# Spectra6PCB_83.net
KiCad netlist of a schematic drawn in EAGLE
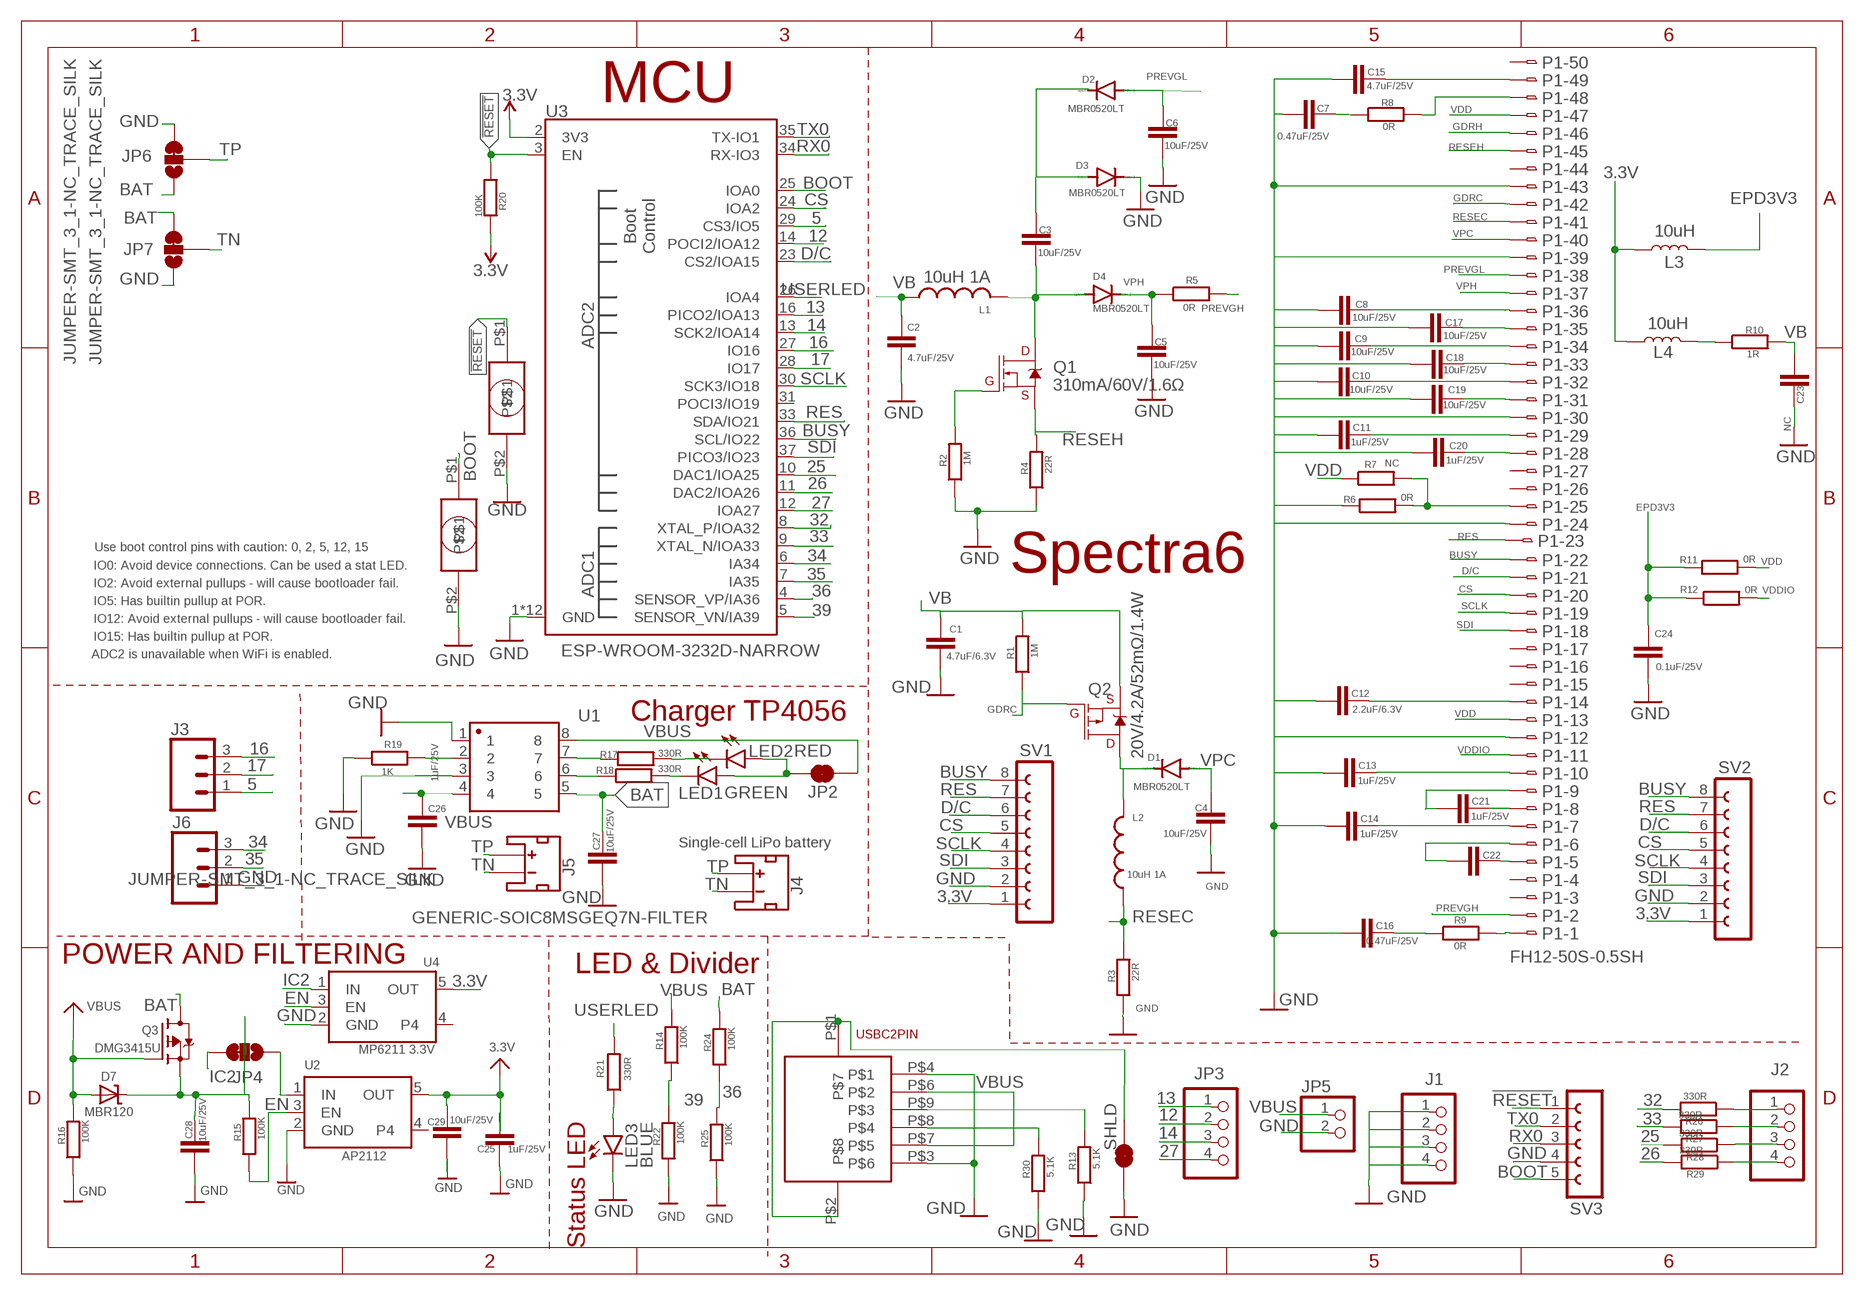
[diagram p0: schematic, sheet 1]

(export (version "E")
  (design (tool "Eeschema 10.0.6"))
  (components
    (comp (ref "C1")
      (value "4.7uF/6.3V")
      (footprint "eagle-import:C0805")
      (libsource (lib "eagle-import") (part "C-EUC0805"))
    )
    (comp (ref "C2")
      (value "4.7uF/25V")
      (footprint "eagle-import:C0805")
      (libsource (lib "eagle-import") (part "C-EUC0805"))
    )
    (comp (ref "C3")
      (value "10uF/25V")
      (footprint "eagle-import:C0805")
      (libsource (lib "eagle-import") (part "C-EUC0805"))
    )
    (comp (ref "C4")
      (value "10uF/25V")
      (footprint "eagle-import:C0805")
      (libsource (lib "eagle-import") (part "C-EUC0805"))
    )
    (comp (ref "C5")
      (value "10uF/25V")
      (footprint "eagle-import:C0805")
      (libsource (lib "eagle-import") (part "C-EUC0805"))
    )
    (comp (ref "C6")
      (value "10uF/25V")
      (footprint "eagle-import:C0805")
      (libsource (lib "eagle-import") (part "C-EUC0805"))
    )
    (comp (ref "C7")
      (value "0.47uF/25V")
      (footprint "eagle-import:C0805")
      (libsource (lib "eagle-import") (part "C-EUC0805"))
    )
    (comp (ref "C8")
      (value "10uF/25V")
      (footprint "eagle-import:C0805")
      (libsource (lib "eagle-import") (part "C-EUC0805"))
    )
    (comp (ref "C9")
      (value "10uF/25V")
      (footprint "eagle-import:C0805")
      (libsource (lib "eagle-import") (part "C-EUC0805"))
    )
    (comp (ref "C10")
      (value "10uF/25V")
      (footprint "eagle-import:C0805")
      (libsource (lib "eagle-import") (part "C-EUC0805"))
    )
    (comp (ref "C11")
      (value "1uF/25V")
      (footprint "eagle-import:C0805")
      (libsource (lib "eagle-import") (part "C-EUC0805"))
    )
    (comp (ref "C12")
      (value "2.2uF/6.3V")
      (footprint "eagle-import:C0805")
      (libsource (lib "eagle-import") (part "C-EUC0805"))
    )
    (comp (ref "C13")
      (value "1uF/25V")
      (footprint "eagle-import:C0805")
      (libsource (lib "eagle-import") (part "C-EUC0805"))
    )
    (comp (ref "C14")
      (value "1uF/25V")
      (footprint "eagle-import:C0805")
      (libsource (lib "eagle-import") (part "C-EUC0805"))
    )
    (comp (ref "C15")
      (value "4.7uF/25V")
      (footprint "eagle-import:C0805")
      (libsource (lib "eagle-import") (part "C-EUC0805"))
    )
    (comp (ref "C16")
      (value "0.47uF/25V")
      (footprint "eagle-import:C0805")
      (libsource (lib "eagle-import") (part "C-EUC0805"))
    )
    (comp (ref "C17")
      (value "10uF/25V")
      (footprint "eagle-import:C0805")
      (libsource (lib "eagle-import") (part "C-EUC0805"))
    )
    (comp (ref "C18")
      (value "10uF/25V")
      (footprint "eagle-import:C0805")
      (libsource (lib "eagle-import") (part "C-EUC0805"))
    )
    (comp (ref "C19")
      (value "10uF/25V")
      (footprint "eagle-import:C0805")
      (libsource (lib "eagle-import") (part "C-EUC0805"))
    )
    (comp (ref "C20")
      (value "1uF/25V")
      (footprint "eagle-import:C0805")
      (libsource (lib "eagle-import") (part "C-EUC0805"))
    )
    (comp (ref "C21")
      (value "1uF/25V")
      (footprint "eagle-import:C0805")
      (libsource (lib "eagle-import") (part "C-EUC0805"))
    )
    (comp (ref "C22")
      (value "1uF/25V")
      (footprint "eagle-import:C0805")
      (libsource (lib "eagle-import") (part "C-EUC0805"))
    )
    (comp (ref "C23")
      (value "NC")
      (footprint "eagle-import:C0805")
      (libsource (lib "eagle-import") (part "C-EUC0805"))
    )
    (comp (ref "C24")
      (value "0.1uF/25V")
      (footprint "eagle-import:C0805")
      (libsource (lib "eagle-import") (part "C-EUC0805"))
    )
    (comp (ref "C25")
      (value "1uF/25V")
      (footprint "eagle-import:C0805")
      (libsource (lib "eagle-import") (part "C-EUC0805"))
    )
    (comp (ref "C26")
      (value "1uF/25V")
      (footprint "eagle-import:C0805")
      (libsource (lib "eagle-import") (part "C-EUC0805"))
    )
    (comp (ref "C27")
      (value "10uF/25V")
      (footprint "eagle-import:C0805")
      (libsource (lib "eagle-import") (part "C-EUC0805"))
    )
    (comp (ref "C28")
      (value "10uF/25V")
      (footprint "eagle-import:C0805")
      (libsource (lib "eagle-import") (part "C-EUC0805"))
    )
    (comp (ref "C29")
      (value "10uF/25V")
      (footprint "eagle-import:C0805")
      (libsource (lib "eagle-import") (part "C-EUC0805"))
    )
    (comp (ref "D1")
      (value "MBR0520LT")
      (footprint "eagle-import:SOD123")
      (libsource (lib "eagle-import") (part "MBR0520LT"))
    )
    (comp (ref "D2")
      (value "MBR0520LT")
      (footprint "eagle-import:SOD123")
      (libsource (lib "eagle-import") (part "MBR0520LT"))
    )
    (comp (ref "D3")
      (value "MBR0520LT")
      (footprint "eagle-import:SOD123")
      (libsource (lib "eagle-import") (part "MBR0520LT"))
    )
    (comp (ref "D4")
      (value "MBR0520LT")
      (footprint "eagle-import:SOD123")
      (libsource (lib "eagle-import") (part "MBR0520LT"))
    )
    (comp (ref "D7")
      (value "MBR120")
      (footprint "eagle-import:SOD-123")
      (libsource (lib "eagle-import") (part "DIODE-SCHOTTKYSOD-123"))
    )
    (comp (ref "J1")
      (value "PINHD-1X4")
      (footprint "eagle-import:1X04")
      (libsource (lib "eagle-import") (part "PINHD-1X4"))
    )
    (comp (ref "J2")
      (value "PINHD-1X4")
      (footprint "eagle-import:1X04")
      (libsource (lib "eagle-import") (part "PINHD-1X4"))
    )
    (comp (ref "J3")
      (value "CONN_03PAD")
      (footprint "eagle-import:1X03_SOLDER_PADS")
      (libsource (lib "eagle-import") (part "CONN_03PAD"))
    )
    (comp (ref "J4")
      (value "JST_2MM_MALE")
      (footprint "eagle-import:JST-2-SMD")
      (libsource (lib "eagle-import") (part "JST_2MM_MALE"))
    )
    (comp (ref "J5")
      (value "NC")
      (footprint "eagle-import:JST-2-SMD")
      (libsource (lib "eagle-import") (part "JST_2MM_MALE"))
    )
    (comp (ref "J6")
      (value "CONN_03PAD")
      (footprint "eagle-import:1X03_SOLDER_PADS")
      (libsource (lib "eagle-import") (part "CONN_03PAD"))
    )
    (comp (ref "JP2")
      (value "JUMPER-SMT_2_NC_TRACE_SILK")
      (footprint "eagle-import:SMT-JUMPER_2_NC_TRACE_SILK")
      (libsource (lib "eagle-import") (part "JUMPER-SMT_2_NC_TRACE_SILK"))
    )
    (comp (ref "JP3")
      (value "PINHD-1X4")
      (footprint "eagle-import:1X04")
      (libsource (lib "eagle-import") (part "PINHD-1X4"))
    )
    (comp (ref "JP4")
      (value "JUMPER-SMT_3_1-NC_TRACE_SILK")
      (footprint "eagle-import:SMT-JUMPER_3_1-NC_TRACE_SILK")
      (libsource (lib "eagle-import") (part "JUMPER-SMT_3_1-NC_TRACE_SILK"))
    )
    (comp (ref "JP5")
      (value "PINHD-1X2")
      (footprint "eagle-import:1X02")
      (libsource (lib "eagle-import") (part "PINHD-1X2"))
    )
    (comp (ref "JP6")
      (value "JUMPER-SMT_3_1-NC_TRACE_SILK")
      (footprint "eagle-import:SMT-JUMPER_3_1-NC_TRACE_SILK")
      (libsource (lib "eagle-import") (part "JUMPER-SMT_3_1-NC_TRACE_SILK"))
    )
    (comp (ref "JP7")
      (value "JUMPER-SMT_3_1-NC_TRACE_SILK")
      (footprint "eagle-import:SMT-JUMPER_3_1-NC_TRACE_SILK")
      (libsource (lib "eagle-import") (part "JUMPER-SMT_3_1-NC_TRACE_SILK"))
    )
    (comp (ref "L1")
      (value "10uH 1A")
      (footprint "eagle-import:L4035M")
      (libsource (lib "eagle-import") (part "L-USL4035M"))
    )
    (comp (ref "L2")
      (value "10uH 1A")
      (footprint "eagle-import:L4035M")
      (libsource (lib "eagle-import") (part "L-USL4035M"))
    )
    (comp (ref "L3")
      (value "10uH")
      (footprint "eagle-import:0805")
      (libsource (lib "eagle-import") (part "INDUCTOR-0805-3.3UH"))
    )
    (comp (ref "L4")
      (value "10uH")
      (footprint "eagle-import:0805")
      (libsource (lib "eagle-import") (part "INDUCTOR-0805-3.3UH"))
    )
    (comp (ref "LED1")
      (value "GREEN")
      (footprint "eagle-import:SML0805")
      (libsource (lib "eagle-import") (part "LEDSML0805"))
    )
    (comp (ref "LED2")
      (value "RED")
      (footprint "eagle-import:SML0805")
      (libsource (lib "eagle-import") (part "LEDSML0805"))
    )
    (comp (ref "LED3")
      (value "BLUE")
      (footprint "eagle-import:SML0805")
      (libsource (lib "eagle-import") (part "LEDSML0805"))
    )
    (comp (ref "P1")
      (value "FH12-50S-0.5SH")
      (footprint "eagle-import:FH12-50S-0.5SH")
      (fields (field (name "MPN") "FH12-50S-0.5SH(55)"))
      (libsource (lib "eagle-import") (part "FH12-50S-0.5SH"))
    )
    (comp (ref "Q1")
      (value "310mA/60V/1.6Ω")
      (footprint "eagle-import:SOT323")
      (libsource (lib "eagle-import") (part "MOSFET-NCH-2N7002PW"))
    )
    (comp (ref "Q2")
      (value "20V/4.2A/52mΩ/1.4W")
      (footprint "eagle-import:SOT23-3")
      (libsource (lib "eagle-import") (part "MOSFET_PCH-DMG2305UX-7"))
    )
    (comp (ref "Q3")
      (value "DMG3415U")
      (footprint "eagle-import:SOT23-R")
      (libsource (lib "eagle-import") (part "MOSFET-P"))
    )
    (comp (ref "R1")
      (value "1M")
      (footprint "eagle-import:M0805")
      (libsource (lib "eagle-import") (part "R-EU_M0805"))
    )
    (comp (ref "R2")
      (value "1M")
      (footprint "eagle-import:M0805")
      (libsource (lib "eagle-import") (part "R-EU_M0805"))
    )
    (comp (ref "R3")
      (value "22R")
      (footprint "eagle-import:M0805")
      (libsource (lib "eagle-import") (part "R-EU_M0805"))
    )
    (comp (ref "R4")
      (value "22R")
      (footprint "eagle-import:M0805")
      (libsource (lib "eagle-import") (part "R-EU_M0805"))
    )
    (comp (ref "R5")
      (value "0R")
      (footprint "eagle-import:M0805")
      (libsource (lib "eagle-import") (part "R-EU_M0805"))
    )
    (comp (ref "R6")
      (value "0R")
      (footprint "eagle-import:M0805")
      (libsource (lib "eagle-import") (part "R-EU_M0805"))
    )
    (comp (ref "R7")
      (value "NC")
      (footprint "eagle-import:M0805")
      (libsource (lib "eagle-import") (part "R-EU_M0805"))
    )
    (comp (ref "R8")
      (value "0R")
      (footprint "eagle-import:M0805")
      (libsource (lib "eagle-import") (part "R-EU_M0805"))
    )
    (comp (ref "R9")
      (value "0R")
      (footprint "eagle-import:M0805")
      (libsource (lib "eagle-import") (part "R-EU_M0805"))
    )
    (comp (ref "R10")
      (value "1R")
      (footprint "eagle-import:M0805")
      (libsource (lib "eagle-import") (part "R-EU_M0805"))
    )
    (comp (ref "R11")
      (value "0R")
      (footprint "eagle-import:M0805")
      (libsource (lib "eagle-import") (part "R-EU_M0805"))
    )
    (comp (ref "R12")
      (value "0R")
      (footprint "eagle-import:M0805")
      (libsource (lib "eagle-import") (part "R-EU_M0805"))
    )
    (comp (ref "R13")
      (value "5.1K")
      (footprint "eagle-import:M0805")
      (libsource (lib "eagle-import") (part "R-EU_M0805"))
    )
    (comp (ref "R14")
      (value "100K")
      (footprint "eagle-import:M0805")
      (libsource (lib "eagle-import") (part "R-EU_M0805"))
    )
    (comp (ref "R15")
      (value "100K")
      (footprint "eagle-import:M0805")
      (libsource (lib "eagle-import") (part "R-EU_M0805"))
    )
    (comp (ref "R16")
      (value "100K")
      (footprint "eagle-import:M0805")
      (libsource (lib "eagle-import") (part "R-EU_M0805"))
    )
    (comp (ref "R17")
      (value "330R")
      (footprint "eagle-import:M0805")
      (libsource (lib "eagle-import") (part "R-EU_M0805"))
    )
    (comp (ref "R18")
      (value "330R")
      (footprint "eagle-import:M0805")
      (libsource (lib "eagle-import") (part "R-EU_M0805"))
    )
    (comp (ref "R19")
      (value "1K")
      (footprint "eagle-import:M0805")
      (libsource (lib "eagle-import") (part "R-EU_M0805"))
    )
    (comp (ref "R20")
      (value "100K")
      (footprint "eagle-import:M0805")
      (libsource (lib "eagle-import") (part "R-EU_M0805"))
    )
    (comp (ref "R21")
      (value "330R")
      (footprint "eagle-import:M0805")
      (libsource (lib "eagle-import") (part "R-EU_M0805"))
    )
    (comp (ref "R22")
      (value "100K")
      (footprint "eagle-import:M0805")
      (libsource (lib "eagle-import") (part "R-EU_M0805"))
    )
    (comp (ref "R24")
      (value "100K")
      (footprint "eagle-import:M0805")
      (libsource (lib "eagle-import") (part "R-EU_M0805"))
    )
    (comp (ref "R25")
      (value "100K")
      (footprint "eagle-import:M0805")
      (libsource (lib "eagle-import") (part "R-EU_M0805"))
    )
    (comp (ref "R26")
      (value "330R")
      (footprint "eagle-import:M0805")
      (libsource (lib "eagle-import") (part "R-EU_M0805"))
    )
    (comp (ref "R27")
      (value "330R")
      (footprint "eagle-import:M0805")
      (libsource (lib "eagle-import") (part "R-EU_M0805"))
    )
    (comp (ref "R28")
      (value "330R")
      (footprint "eagle-import:M0805")
      (libsource (lib "eagle-import") (part "R-EU_M0805"))
    )
    (comp (ref "R29")
      (value "330R")
      (footprint "eagle-import:M0805")
      (libsource (lib "eagle-import") (part "R-EU_M0805"))
    )
    (comp (ref "R30")
      (value "5.1K")
      (footprint "eagle-import:M0805")
      (libsource (lib "eagle-import") (part "R-EU_M0805"))
    )
    (comp (ref "S3")
      (value "TACTILE")
      (footprint "eagle-import:TACTILE")
      (libsource (lib "eagle-import") (part "TACTILE"))
    )
    (comp (ref "S4")
      (value "TACTILE")
      (footprint "eagle-import:TACTILE")
      (libsource (lib "eagle-import") (part "TACTILE"))
    )
    (comp (ref "SHLD")
      (value "SHLD")
      (footprint "eagle-import:SMT-JUMPER_2_NC_TRACE_NO-SILK")
      (libsource (lib "eagle-import") (part "JUMPER-SMT_2_NC_TRACE_NO-SILK"))
    )
    (comp (ref "SV1")
      (value "FE08-1")
      (footprint "eagle-import:FE08")
      (libsource (lib "eagle-import") (part "FE08-1"))
    )
    (comp (ref "SV2")
      (value "FE08-1")
      (footprint "eagle-import:FE08")
      (libsource (lib "eagle-import") (part "FE08-1"))
    )
    (comp (ref "SV3")
      (value "FE05-1")
      (footprint "eagle-import:FE05-1")
      (libsource (lib "eagle-import") (part "FE05-1"))
    )
    (comp (ref "U$4")
      (value "USBC6PIN")
      (footprint "eagle-import:USBC6PIN")
      (libsource (lib "eagle-import") (part "USBC6PIN"))
    )
    (comp (ref "U1")
      (value "GENERIC-SOIC8MSGEQ7N-FILTER")
      (footprint "eagle-import:SO08")
      (libsource (lib "eagle-import") (part "GENERIC-SOIC8MSGEQ7N-FILTER"))
    )
    (comp (ref "U2")
      (value "AP2112")
      (footprint "eagle-import:SOT23-5")
      (libsource (lib "eagle-import") (part "VREG_SOT23-5"))
    )
    (comp (ref "U3")
      (value "ESP-WROOM-3232D-NARROW")
      (footprint "eagle-import:ESP-WROOM-32D-NARROW")
      (libsource (lib "eagle-import") (part "ESP-WROOM-3232D-NARROW"))
    )
    (comp (ref "U4")
      (value "MP6211 3.3V")
      (footprint "eagle-import:SOT23-5")
      (libsource (lib "eagle-import") (part "VREG_SOT23-5"))
    )
  )
  (nets
    (net (code "1") (name "/5") (class "Default")
      (node (ref "J3") (pin "1") (pinfunction "1_1") (pintype "passive"))
      (node (ref "U3") (pin "29") (pinfunction "CS3/IO5_29") (pintype "bidirectional"))
    )
    (net (code "2") (name "/12") (class "Default")
      (node (ref "JP3") (pin "2") (pinfunction "2_2") (pintype "passive"))
      (node (ref "U3") (pin "14") (pinfunction "POCI2/IOA12_14") (pintype "bidirectional"))
    )
    (net (code "3") (name "/13") (class "Default")
      (node (ref "JP3") (pin "1") (pinfunction "1_1") (pintype "passive"))
      (node (ref "U3") (pin "16") (pinfunction "PICO2/IOA13_16") (pintype "bidirectional"))
    )
    (net (code "4") (name "/14") (class "Default")
      (node (ref "JP3") (pin "3") (pinfunction "3_3") (pintype "passive"))
      (node (ref "U3") (pin "13") (pinfunction "SCK2/IOA14_13") (pintype "bidirectional"))
    )
    (net (code "5") (name "/16") (class "Default")
      (node (ref "J3") (pin "3") (pinfunction "3_3") (pintype "passive"))
      (node (ref "U3") (pin "27") (pinfunction "IO16_27") (pintype "bidirectional"))
    )
    (net (code "6") (name "/17") (class "Default")
      (node (ref "J3") (pin "2") (pinfunction "2_2") (pintype "passive"))
      (node (ref "U3") (pin "28") (pinfunction "IO17_28") (pintype "bidirectional"))
    )
    (net (code "7") (name "/25") (class "Default")
      (node (ref "R28") (pin "2") (pinfunction "2_2") (pintype "passive"))
      (node (ref "U3") (pin "10") (pinfunction "DAC1/IOA25_10") (pintype "bidirectional"))
    )
    (net (code "8") (name "/26") (class "Default")
      (node (ref "R29") (pin "2") (pinfunction "2_2") (pintype "passive"))
      (node (ref "U3") (pin "11") (pinfunction "DAC2/IOA26_11") (pintype "bidirectional"))
    )
    (net (code "9") (name "/27") (class "Default")
      (node (ref "JP3") (pin "4") (pinfunction "4_4") (pintype "passive"))
      (node (ref "U3") (pin "12") (pinfunction "IOA27_12") (pintype "bidirectional"))
    )
    (net (code "10") (name "/32") (class "Default")
      (node (ref "R26") (pin "2") (pinfunction "2_2") (pintype "passive"))
      (node (ref "U3") (pin "8") (pinfunction "XTAL_P/IOA32_8") (pintype "bidirectional"))
    )
    (net (code "11") (name "/33") (class "Default")
      (node (ref "R27") (pin "2") (pinfunction "2_2") (pintype "passive"))
      (node (ref "U3") (pin "9") (pinfunction "XTAL_N/IOA33_9") (pintype "bidirectional"))
    )
    (net (code "12") (name "/34") (class "Default")
      (node (ref "J6") (pin "3") (pinfunction "3_3") (pintype "passive"))
      (node (ref "U3") (pin "6") (pinfunction "IA34_6") (pintype "bidirectional"))
    )
    (net (code "13") (name "/35") (class "Default")
      (node (ref "J6") (pin "2") (pinfunction "2_2") (pintype "passive"))
      (node (ref "U3") (pin "7") (pinfunction "IA35_7") (pintype "bidirectional"))
    )
    (net (code "14") (name "/36") (class "Default")
      (node (ref "R24") (pin "1") (pinfunction "1_1") (pintype "passive"))
      (node (ref "R25") (pin "2") (pinfunction "2_2") (pintype "passive"))
      (node (ref "U3") (pin "4") (pinfunction "SENSOR_VP/IA36_4") (pintype "bidirectional"))
    )
    (net (code "15") (name "/39") (class "Default")
      (node (ref "R14") (pin "1") (pinfunction "1_1") (pintype "passive"))
      (node (ref "R22") (pin "2") (pinfunction "2_2") (pintype "passive"))
      (node (ref "U3") (pin "5") (pinfunction "SENSOR_VN/IA39_5") (pintype "bidirectional"))
    )
    (net (code "16") (name "/BOOT") (class "Default")
      (node (ref "S3") (pin "P$1") (pinfunction "P$1_P$1") (pintype "bidirectional"))
      (node (ref "SV3") (pin "5") (pinfunction "5_5") (pintype "passive"))
      (node (ref "U3") (pin "25") (pinfunction "IOA0_25") (pintype "bidirectional"))
    )
    (net (code "17") (name "/BUSY") (class "Default")
      (node (ref "P1") (pin "22") (pinfunction "1_22") (pintype "passive"))
      (node (ref "SV1") (pin "8") (pinfunction "8_8") (pintype "passive"))
      (node (ref "SV2") (pin "8") (pinfunction "8_8") (pintype "passive"))
      (node (ref "U3") (pin "36") (pinfunction "SCL/IO22_36") (pintype "bidirectional"))
    )
    (net (code "18") (name "/CS") (class "Default")
      (node (ref "P1") (pin "20") (pinfunction "1_20") (pintype "passive"))
      (node (ref "SV1") (pin "5") (pinfunction "5_5") (pintype "passive"))
      (node (ref "SV2") (pin "5") (pinfunction "5_5") (pintype "passive"))
      (node (ref "U3") (pin "24") (pinfunction "IOA2_24") (pintype "bidirectional"))
    )
    (net (code "19") (name "/D{slash}C") (class "Default")
      (node (ref "P1") (pin "21") (pinfunction "1_21") (pintype "passive"))
      (node (ref "SV1") (pin "6") (pinfunction "6_6") (pintype "passive"))
      (node (ref "SV2") (pin "6") (pinfunction "6_6") (pintype "passive"))
      (node (ref "U3") (pin "23") (pinfunction "CS2/IOA15_23") (pintype "bidirectional"))
    )
    (net (code "20") (name "/EN") (class "Default")
      (node (ref "R15") (pin "1") (pinfunction "1_1") (pintype "passive"))
      (node (ref "U2") (pin "3") (pinfunction "EN_3") (pintype "input"))
      (node (ref "U4") (pin "3") (pinfunction "EN_3") (pintype "input"))
    )
    (net (code "21") (name "/EPD3V3") (class "Default")
      (node (ref "C24") (pin "2") (pinfunction "2_2") (pintype "passive"))
      (node (ref "L3") (pin "2") (pinfunction "2_2") (pintype "passive"))
      (node (ref "R11") (pin "1") (pinfunction "1_1") (pintype "passive"))
      (node (ref "R12") (pin "1") (pinfunction "1_1") (pintype "passive"))
    )
    (net (code "22") (name "/GDRC") (class "Default")
      (node (ref "P1") (pin "42") (pinfunction "1_42") (pintype "passive"))
      (node (ref "Q2") (pin "1") (pinfunction "G_1") (pintype "bidirectional"))
      (node (ref "R1") (pin "1") (pinfunction "1_1") (pintype "passive"))
    )
    (net (code "23") (name "/GDRH") (class "Default")
      (node (ref "P1") (pin "46") (pinfunction "1_46") (pintype "passive"))
      (node (ref "Q1") (pin "1") (pinfunction "G_1") (pintype "bidirectional"))
      (node (ref "R2") (pin "2") (pinfunction "2_2") (pintype "passive"))
    )
    (net (code "24") (name "/IC2") (class "Default")
      (node (ref "JP4") (pin "3") (pinfunction "3_3") (pintype "passive"))
      (node (ref "U4") (pin "1") (pinfunction "IN_1") (pintype "power_in"))
    )
    (net (code "25") (name "/PREVGH") (class "Default")
      (node (ref "P1") (pin "2") (pinfunction "1_2") (pintype "passive"))
      (node (ref "R5") (pin "2") (pinfunction "2_2") (pintype "passive"))
    )
    (net (code "26") (name "/PREVGL") (class "Default")
      (node (ref "C6") (pin "1") (pinfunction "1_1") (pintype "passive"))
      (node (ref "D2") (pin "A") (pinfunction "A_A") (pintype "passive"))
      (node (ref "P1") (pin "38") (pinfunction "1_38") (pintype "passive"))
    )
    (net (code "27") (name "/RES") (class "Default")
      (node (ref "P1") (pin "23") (pinfunction "1_23") (pintype "passive"))
      (node (ref "SV1") (pin "7") (pinfunction "7_7") (pintype "passive"))
      (node (ref "SV2") (pin "7") (pinfunction "7_7") (pintype "passive"))
      (node (ref "U3") (pin "33") (pinfunction "SDA/IO21_33") (pintype "bidirectional"))
    )
    (net (code "28") (name "/RESEC") (class "Default")
      (node (ref "L2") (pin "1") (pinfunction "1_1") (pintype "passive"))
      (node (ref "P1") (pin "41") (pinfunction "1_41") (pintype "passive"))
      (node (ref "R3") (pin "2") (pinfunction "2_2") (pintype "passive"))
    )
    (net (code "29") (name "/RESEH") (class "Default")
      (node (ref "P1") (pin "45") (pinfunction "1_45") (pintype "passive"))
      (node (ref "Q1") (pin "2") (pinfunction "S_2") (pintype "bidirectional"))
      (node (ref "R4") (pin "2") (pinfunction "2_2") (pintype "passive"))
    )
    (net (code "30") (name "/RX0") (class "Default")
      (node (ref "SV3") (pin "3") (pinfunction "3_3") (pintype "passive"))
      (node (ref "U3") (pin "34") (pinfunction "RX-IO3_34") (pintype "bidirectional"))
    )
    (net (code "31") (name "/SCLK") (class "Default")
      (node (ref "P1") (pin "19") (pinfunction "1_19") (pintype "passive"))
      (node (ref "SV1") (pin "4") (pinfunction "4_4") (pintype "passive"))
      (node (ref "SV2") (pin "4") (pinfunction "4_4") (pintype "passive"))
      (node (ref "U3") (pin "30") (pinfunction "SCK3/IO18_30") (pintype "bidirectional"))
    )
    (net (code "32") (name "/SDI") (class "Default")
      (node (ref "P1") (pin "18") (pinfunction "1_18") (pintype "passive"))
      (node (ref "SV1") (pin "3") (pinfunction "3_3") (pintype "passive"))
      (node (ref "SV2") (pin "3") (pinfunction "3_3") (pintype "passive"))
      (node (ref "U3") (pin "37") (pinfunction "PICO3/IO23_37") (pintype "bidirectional"))
    )
    (net (code "33") (name "/TN") (class "Default")
      (node (ref "J4") (pin "1") (pinfunction "-_1") (pintype "bidirectional"))
      (node (ref "J5") (pin "1") (pinfunction "-_1") (pintype "bidirectional"))
      (node (ref "JP7") (pin "2") (pinfunction "2_2") (pintype "passive"))
    )
    (net (code "34") (name "/TP") (class "Default")
      (node (ref "J4") (pin "2") (pinfunction "+_2") (pintype "bidirectional"))
      (node (ref "J5") (pin "2") (pinfunction "+_2") (pintype "bidirectional"))
      (node (ref "JP6") (pin "2") (pinfunction "2_2") (pintype "passive"))
    )
    (net (code "35") (name "/TX0") (class "Default")
      (node (ref "SV3") (pin "2") (pinfunction "2_2") (pintype "passive"))
      (node (ref "U3") (pin "35") (pinfunction "TX-IO1_35") (pintype "bidirectional"))
    )
    (net (code "36") (name "/USERLED") (class "Default")
      (node (ref "R21") (pin "2") (pinfunction "2_2") (pintype "passive"))
      (node (ref "U3") (pin "26") (pinfunction "IOA4_26") (pintype "bidirectional"))
    )
    (net (code "37") (name "/VB") (class "Default")
      (node (ref "C2") (pin "2") (pinfunction "2_2") (pintype "passive"))
      (node (ref "C23") (pin "1") (pinfunction "1_1") (pintype "passive"))
      (node (ref "L1") (pin "1") (pinfunction "1_1") (pintype "passive"))
      (node (ref "R10") (pin "2") (pinfunction "2_2") (pintype "passive"))
    )
    (net (code "38") (name "/VDD") (class "Default")
      (node (ref "P1") (pin "13") (pinfunction "1_13") (pintype "passive"))
      (node (ref "P1") (pin "47") (pinfunction "1_47") (pintype "passive"))
      (node (ref "R11") (pin "2") (pinfunction "2_2") (pintype "passive"))
      (node (ref "R7") (pin "1") (pinfunction "1_1") (pintype "passive"))
    )
    (net (code "39") (name "/VDDIO") (class "Default")
      (node (ref "P1") (pin "11") (pinfunction "1_11") (pintype "passive"))
      (node (ref "R12") (pin "2") (pinfunction "2_2") (pintype "passive"))
    )
    (net (code "40") (name "/VPC") (class "Default")
      (node (ref "C4") (pin "2") (pinfunction "2_2") (pintype "passive"))
      (node (ref "D1") (pin "A") (pinfunction "A_A") (pintype "passive"))
      (node (ref "P1") (pin "40") (pinfunction "1_40") (pintype "passive"))
    )
    (net (code "41") (name "/VPH") (class "Default")
      (node (ref "C5") (pin "1") (pinfunction "1_1") (pintype "passive"))
      (node (ref "D4") (pin "C") (pinfunction "C_C") (pintype "passive"))
      (node (ref "P1") (pin "37") (pinfunction "1_37") (pintype "passive"))
      (node (ref "R5") (pin "1") (pinfunction "1_1") (pintype "passive"))
    )
    (net (code "42") (name "/~{RESET}") (class "Default")
      (node (ref "R20") (pin "1") (pinfunction "1_1") (pintype "passive"))
      (node (ref "S4") (pin "P$1") (pinfunction "P$1_P$1") (pintype "bidirectional"))
      (node (ref "SV3") (pin "1") (pinfunction "1_1") (pintype "passive"))
      (node (ref "U3") (pin "3") (pinfunction "EN_3") (pintype "bidirectional"))
    )
    (net (code "43") (name "3.3V") (class "Default")
      (node (ref "C25") (pin "2") (pinfunction "2_2") (pintype "passive"))
      (node (ref "C29") (pin "2") (pinfunction "2_2") (pintype "passive"))
      (node (ref "L3") (pin "1") (pinfunction "1_1") (pintype "passive"))
      (node (ref "L4") (pin "1") (pinfunction "1_1") (pintype "passive"))
      (node (ref "R20") (pin "2") (pinfunction "2_2") (pintype "passive"))
      (node (ref "SV1") (pin "1") (pinfunction "1_1") (pintype "passive"))
      (node (ref "SV2") (pin "1") (pinfunction "1_1") (pintype "passive"))
      (node (ref "U2") (pin "5") (pinfunction "OUT_5") (pintype "power_in"))
      (node (ref "U3") (pin "2") (pinfunction "3V3_2") (pintype "bidirectional"))
      (node (ref "U4") (pin "5") (pinfunction "OUT_5") (pintype "power_in"))
    )
    (net (code "44") (name "BAT") (class "Default")
      (node (ref "C27") (pin "2") (pinfunction "2_2") (pintype "passive"))
      (node (ref "JP6") (pin "1") (pinfunction "1_1") (pintype "passive"))
      (node (ref "JP7") (pin "3") (pinfunction "3_3") (pintype "passive"))
      (node (ref "Q3") (pin "3") (pinfunction "D_3") (pintype "passive"))
      (node (ref "R24") (pin "2") (pinfunction "2_2") (pintype "passive"))
      (node (ref "U1") (pin "5") (pinfunction "5_5") (pintype "bidirectional"))
    )
    (net (code "45") (name "GND") (class "Default")
      (node (ref "C1") (pin "1") (pinfunction "1_1") (pintype "passive"))
      (node (ref "C10") (pin "1") (pinfunction "1_1") (pintype "passive"))
      (node (ref "C11") (pin "1") (pinfunction "1_1") (pintype "passive"))
      (node (ref "C12") (pin "1") (pinfunction "1_1") (pintype "passive"))
      (node (ref "C13") (pin "1") (pinfunction "1_1") (pintype "passive"))
      (node (ref "C14") (pin "1") (pinfunction "1_1") (pintype "passive"))
      (node (ref "C15") (pin "1") (pinfunction "1_1") (pintype "passive"))
      (node (ref "C16") (pin "1") (pinfunction "1_1") (pintype "passive"))
      (node (ref "C17") (pin "1") (pinfunction "1_1") (pintype "passive"))
      (node (ref "C18") (pin "1") (pinfunction "1_1") (pintype "passive"))
      (node (ref "C19") (pin "1") (pinfunction "1_1") (pintype "passive"))
      (node (ref "C2") (pin "1") (pinfunction "1_1") (pintype "passive"))
      (node (ref "C20") (pin "1") (pinfunction "1_1") (pintype "passive"))
      (node (ref "C23") (pin "2") (pinfunction "2_2") (pintype "passive"))
      (node (ref "C24") (pin "1") (pinfunction "1_1") (pintype "passive"))
      (node (ref "C25") (pin "1") (pinfunction "1_1") (pintype "passive"))
      (node (ref "C26") (pin "1") (pinfunction "1_1") (pintype "passive"))
      (node (ref "C27") (pin "1") (pinfunction "1_1") (pintype "passive"))
      (node (ref "C28") (pin "1") (pinfunction "1_1") (pintype "passive"))
      (node (ref "C29") (pin "1") (pinfunction "1_1") (pintype "passive"))
      (node (ref "C4") (pin "1") (pinfunction "1_1") (pintype "passive"))
      (node (ref "C5") (pin "2") (pinfunction "2_2") (pintype "passive"))
      (node (ref "C6") (pin "2") (pinfunction "2_2") (pintype "passive"))
      (node (ref "C7") (pin "1") (pinfunction "1_1") (pintype "passive"))
      (node (ref "C8") (pin "1") (pinfunction "1_1") (pintype "passive"))
      (node (ref "C9") (pin "1") (pinfunction "1_1") (pintype "passive"))
      (node (ref "D3") (pin "C") (pinfunction "C_C") (pintype "passive"))
      (node (ref "J1") (pin "1") (pinfunction "1_1") (pintype "passive"))
      (node (ref "J1") (pin "2") (pinfunction "2_2") (pintype "passive"))
      (node (ref "J1") (pin "3") (pinfunction "3_3") (pintype "passive"))
      (node (ref "J1") (pin "4") (pinfunction "4_4") (pintype "passive"))
      (node (ref "J6") (pin "1") (pinfunction "1_1") (pintype "passive"))
      (node (ref "JP5") (pin "2") (pinfunction "2_2") (pintype "passive"))
      (node (ref "JP6") (pin "3") (pinfunction "3_3") (pintype "passive"))
      (node (ref "JP7") (pin "1") (pinfunction "1_1") (pintype "passive"))
      (node (ref "LED3") (pin "C") (pinfunction "C_C") (pintype "passive"))
      (node (ref "P1") (pin "24") (pinfunction "1_24") (pintype "passive"))
      (node (ref "P1") (pin "30") (pinfunction "1_30") (pintype "passive"))
      (node (ref "P1") (pin "39") (pinfunction "1_39") (pintype "passive"))
      (node (ref "P1") (pin "43") (pinfunction "1_43") (pintype "passive"))
      (node (ref "R13") (pin "1") (pinfunction "1_1") (pintype "passive"))
      (node (ref "R16") (pin "1") (pinfunction "1_1") (pintype "passive"))
      (node (ref "R19") (pin "1") (pinfunction "1_1") (pintype "passive"))
      (node (ref "R2") (pin "1") (pinfunction "1_1") (pintype "passive"))
      (node (ref "R22") (pin "1") (pinfunction "1_1") (pintype "passive"))
      (node (ref "R25") (pin "1") (pinfunction "1_1") (pintype "passive"))
      (node (ref "R3") (pin "1") (pinfunction "1_1") (pintype "passive"))
      (node (ref "R30") (pin "1") (pinfunction "1_1") (pintype "passive"))
      (node (ref "R4") (pin "1") (pinfunction "1_1") (pintype "passive"))
      (node (ref "R6") (pin "1") (pinfunction "1_1") (pintype "passive"))
      (node (ref "S3") (pin "P$2") (pinfunction "P$2_P$2") (pintype "bidirectional"))
      (node (ref "S4") (pin "P$2") (pinfunction "P$2_P$2") (pintype "bidirectional"))
      (node (ref "SHLD") (pin "1") (pinfunction "1_1") (pintype "passive"))
      (node (ref "SV1") (pin "2") (pinfunction "2_2") (pintype "passive"))
      (node (ref "SV2") (pin "2") (pinfunction "2_2") (pintype "passive"))
      (node (ref "SV3") (pin "4") (pinfunction "4_4") (pintype "passive"))
      (node (ref "U$4") (pin "P$3") (pinfunction "P$6_P$3") (pintype "bidirectional"))
      (node (ref "U$4") (pin "P$4") (pinfunction "P$1_P$4") (pintype "bidirectional"))
      (node (ref "U1") (pin "1") (pinfunction "1_1") (pintype "bidirectional"))
      (node (ref "U1") (pin "3") (pinfunction "3_3") (pintype "bidirectional"))
      (node (ref "U2") (pin "2") (pinfunction "GND_2") (pintype "power_in"))
      (node (ref "U3") (pin "1") (pinfunction "GND_1") (pintype "bidirectional"))
      (node (ref "U3") (pin "15") (pinfunction "GND_15") (pintype "bidirectional"))
      (node (ref "U3") (pin "38") (pinfunction "GND_38") (pintype "bidirectional"))
      (node (ref "U3") (pin "GND1") (pinfunction "GND_GND1") (pintype "bidirectional"))
      (node (ref "U3") (pin "GNDT1") (pinfunction "GND_GNDT1") (pintype "bidirectional"))
      (node (ref "U3") (pin "GNDT2") (pinfunction "GND_GNDT2") (pintype "bidirectional"))
      (node (ref "U3") (pin "GNDT3") (pinfunction "GND_GNDT3") (pintype "bidirectional"))
      (node (ref "U3") (pin "GNDT4") (pinfunction "GND_GNDT4") (pintype "bidirectional"))
      (node (ref "U3") (pin "GNDT5") (pinfunction "GND_GNDT5") (pintype "bidirectional"))
      (node (ref "U3") (pin "GNDT6") (pinfunction "GND_GNDT6") (pintype "bidirectional"))
      (node (ref "U3") (pin "GNDT7") (pinfunction "GND_GNDT7") (pintype "bidirectional"))
      (node (ref "U3") (pin "GNDT8") (pinfunction "GND_GNDT8") (pintype "bidirectional"))
      (node (ref "U4") (pin "2") (pinfunction "GND_2") (pintype "power_in"))
    )
    (net (code "46") (name "Net-(C3-Pad1)") (class "Default")
      (node (ref "C3") (pin "1") (pinfunction "1_1") (pintype "passive"))
      (node (ref "D2") (pin "C") (pinfunction "C_C") (pintype "passive"))
      (node (ref "D3") (pin "A") (pinfunction "A_A") (pintype "passive"))
    )
    (net (code "47") (name "Net-(C7-Pad2)") (class "Default")
      (node (ref "C7") (pin "2") (pinfunction "2_2") (pintype "passive"))
      (node (ref "R8") (pin "1") (pinfunction "1_1") (pintype "passive"))
    )
    (net (code "48") (name "Net-(C16-Pad2)") (class "Default")
      (node (ref "C16") (pin "2") (pinfunction "2_2") (pintype "passive"))
      (node (ref "R9") (pin "1") (pinfunction "1_1") (pintype "passive"))
    )
    (net (code "49") (name "Net-(J2-Pad1)") (class "Default")
      (node (ref "J2") (pin "1") (pinfunction "1_1") (pintype "passive"))
      (node (ref "R26") (pin "1") (pinfunction "1_1") (pintype "passive"))
    )
    (net (code "50") (name "Net-(J2-Pad2)") (class "Default")
      (node (ref "J2") (pin "2") (pinfunction "2_2") (pintype "passive"))
      (node (ref "R27") (pin "1") (pinfunction "1_1") (pintype "passive"))
    )
    (net (code "51") (name "Net-(J2-Pad3)") (class "Default")
      (node (ref "J2") (pin "3") (pinfunction "3_3") (pintype "passive"))
      (node (ref "R28") (pin "1") (pinfunction "1_1") (pintype "passive"))
    )
    (net (code "52") (name "Net-(J2-Pad4)") (class "Default")
      (node (ref "J2") (pin "4") (pinfunction "4_4") (pintype "passive"))
      (node (ref "R29") (pin "1") (pinfunction "1_1") (pintype "passive"))
    )
    (net (code "53") (name "Net-(JP2-Pad2)") (class "Default")
      (node (ref "JP2") (pin "2") (pinfunction "2_2") (pintype "passive"))
      (node (ref "LED1") (pin "A") (pinfunction "A_A") (pintype "passive"))
      (node (ref "LED2") (pin "A") (pinfunction "A_A") (pintype "passive"))
    )
    (net (code "54") (name "Net-(L4-Pad2)") (class "Default")
      (node (ref "L4") (pin "2") (pinfunction "2_2") (pintype "passive"))
      (node (ref "R10") (pin "1") (pinfunction "1_1") (pintype "passive"))
    )
    (net (code "55") (name "Net-(LED1-PadC)") (class "Default")
      (node (ref "LED1") (pin "C") (pinfunction "C_C") (pintype "passive"))
      (node (ref "R18") (pin "2") (pinfunction "2_2") (pintype "passive"))
    )
    (net (code "56") (name "Net-(LED2-PadC)") (class "Default")
      (node (ref "LED2") (pin "C") (pinfunction "C_C") (pintype "passive"))
      (node (ref "R17") (pin "2") (pinfunction "2_2") (pintype "passive"))
    )
    (net (code "57") (name "Net-(LED3-PadA)") (class "Default")
      (node (ref "LED3") (pin "A") (pinfunction "A_A") (pintype "passive"))
      (node (ref "R21") (pin "1") (pinfunction "1_1") (pintype "passive"))
    )
    (net (code "58") (name "Net-(P1-Pad1)") (class "Default")
      (node (ref "P1") (pin "1") (pinfunction "1_1") (pintype "passive"))
      (node (ref "R9") (pin "2") (pinfunction "2_2") (pintype "passive"))
    )
    (net (code "59") (name "Net-(P1AA-1)") (class "Default")
      (node (ref "C18") (pin "2") (pinfunction "2_2") (pintype "passive"))
      (node (ref "P1") (pin "33") (pinfunction "1_33") (pintype "passive"))
    )
    (net (code "60") (name "Net-(P1AB-1)") (class "Default")
      (node (ref "C9") (pin "2") (pinfunction "2_2") (pintype "passive"))
      (node (ref "P1") (pin "34") (pinfunction "1_34") (pintype "passive"))
    )
    (net (code "61") (name "Net-(P1AC-1)") (class "Default")
      (node (ref "C17") (pin "2") (pinfunction "2_2") (pintype "passive"))
      (node (ref "P1") (pin "35") (pinfunction "1_35") (pintype "passive"))
    )
    (net (code "62") (name "Net-(P1AD-1)") (class "Default")
      (node (ref "C8") (pin "2") (pinfunction "2_2") (pintype "passive"))
      (node (ref "P1") (pin "36") (pinfunction "1_36") (pintype "passive"))
    )
    (net (code "63") (name "Net-(P1AQ-1)") (class "Default")
      (node (ref "P1") (pin "48") (pinfunction "1_48") (pintype "passive"))
      (node (ref "R8") (pin "2") (pinfunction "2_2") (pintype "passive"))
    )
    (net (code "64") (name "Net-(P1AR-1)") (class "Default")
      (node (ref "C15") (pin "2") (pinfunction "2_2") (pintype "passive"))
      (node (ref "P1") (pin "49") (pinfunction "1_49") (pintype "passive"))
    )
    (net (code "65") (name "Net-(P1AS-1)") (class "Default")
      (node (ref "C22") (pin "2") (pinfunction "2_2") (pintype "passive"))
      (node (ref "P1") (pin "5") (pinfunction "1_5") (pintype "passive"))
    )
    (net (code "66") (name "Net-(P1AU-1)") (class "Default")
      (node (ref "C22") (pin "1") (pinfunction "1_1") (pintype "passive"))
      (node (ref "P1") (pin "6") (pinfunction "1_6") (pintype "passive"))
    )
    (net (code "67") (name "Net-(P1AV-1)") (class "Default")
      (node (ref "C14") (pin "2") (pinfunction "2_2") (pintype "passive"))
      (node (ref "P1") (pin "7") (pinfunction "1_7") (pintype "passive"))
    )
    (net (code "68") (name "Net-(P1AW-1)") (class "Default")
      (node (ref "C21") (pin "2") (pinfunction "2_2") (pintype "passive"))
      (node (ref "P1") (pin "8") (pinfunction "1_8") (pintype "passive"))
    )
    (net (code "69") (name "Net-(P1AX-1)") (class "Default")
      (node (ref "C21") (pin "1") (pinfunction "1_1") (pintype "passive"))
      (node (ref "P1") (pin "9") (pinfunction "1_9") (pintype "passive"))
    )
    (net (code "70") (name "Net-(P1B-1)") (class "Default")
      (node (ref "C13") (pin "2") (pinfunction "2_2") (pintype "passive"))
      (node (ref "P1") (pin "10") (pinfunction "1_10") (pintype "passive"))
    )
    (net (code "71") (name "Net-(P1F-1)") (class "Default")
      (node (ref "C12") (pin "2") (pinfunction "2_2") (pintype "passive"))
      (node (ref "P1") (pin "14") (pinfunction "1_14") (pintype "passive"))
    )
    (net (code "72") (name "Net-(P1R-1)") (class "Default")
      (node (ref "P1") (pin "25") (pinfunction "1_25") (pintype "passive"))
      (node (ref "R6") (pin "2") (pinfunction "2_2") (pintype "passive"))
      (node (ref "R7") (pin "2") (pinfunction "2_2") (pintype "passive"))
    )
    (net (code "73") (name "Net-(P1U-1)") (class "Default")
      (node (ref "C20") (pin "2") (pinfunction "2_2") (pintype "passive"))
      (node (ref "P1") (pin "28") (pinfunction "1_28") (pintype "passive"))
    )
    (net (code "74") (name "Net-(P1V-1)") (class "Default")
      (node (ref "C11") (pin "2") (pinfunction "2_2") (pintype "passive"))
      (node (ref "P1") (pin "29") (pinfunction "1_29") (pintype "passive"))
    )
    (net (code "75") (name "Net-(P1Y-1)") (class "Default")
      (node (ref "C19") (pin "2") (pinfunction "2_2") (pintype "passive"))
      (node (ref "P1") (pin "31") (pinfunction "1_31") (pintype "passive"))
    )
    (net (code "76") (name "Net-(P1Z-1)") (class "Default")
      (node (ref "C10") (pin "2") (pinfunction "2_2") (pintype "passive"))
      (node (ref "P1") (pin "32") (pinfunction "1_32") (pintype "passive"))
    )
    (net (code "77") (name "Net-(Q1-D)") (class "Default")
      (node (ref "C3") (pin "2") (pinfunction "2_2") (pintype "passive"))
      (node (ref "D4") (pin "A") (pinfunction "A_A") (pintype "passive"))
      (node (ref "L1") (pin "2") (pinfunction "2_2") (pintype "passive"))
      (node (ref "Q1") (pin "3") (pinfunction "D_3") (pintype "bidirectional"))
    )
    (net (code "78") (name "Net-(Q2-D)") (class "Default")
      (node (ref "D1") (pin "C") (pinfunction "C_C") (pintype "passive"))
      (node (ref "L2") (pin "2") (pinfunction "2_2") (pintype "passive"))
      (node (ref "Q2") (pin "3") (pinfunction "D_3") (pintype "bidirectional"))
    )
    (net (code "79") (name "Net-(Q2-S)") (class "Default")
      (node (ref "C1") (pin "2") (pinfunction "2_2") (pintype "passive"))
      (node (ref "Q2") (pin "2") (pinfunction "S_2") (pintype "bidirectional"))
      (node (ref "R1") (pin "2") (pinfunction "2_2") (pintype "passive"))
    )
    (net (code "80") (name "Net-(Q3-S)") (class "Default")
      (node (ref "C28") (pin "2") (pinfunction "2_2") (pintype "passive"))
      (node (ref "D7") (pin "C") (pinfunction "C_C") (pintype "passive"))
      (node (ref "JP4") (pin "2") (pinfunction "2_2") (pintype "passive"))
      (node (ref "Q3") (pin "2") (pinfunction "S_2") (pintype "passive"))
      (node (ref "R15") (pin "2") (pinfunction "2_2") (pintype "passive"))
    )
    (net (code "81") (name "Net-(R17-Pad1)") (class "Default")
      (node (ref "R17") (pin "1") (pinfunction "1_1") (pintype "passive"))
      (node (ref "U1") (pin "7") (pinfunction "7_7") (pintype "bidirectional"))
    )
    (net (code "82") (name "Net-(R18-Pad1)") (class "Default")
      (node (ref "R18") (pin "1") (pinfunction "1_1") (pintype "passive"))
      (node (ref "U1") (pin "6") (pinfunction "6_6") (pintype "bidirectional"))
    )
    (net (code "83") (name "Net-(R19-Pad2)") (class "Default")
      (node (ref "R19") (pin "2") (pinfunction "2_2") (pintype "passive"))
      (node (ref "U1") (pin "2") (pinfunction "2_2") (pintype "bidirectional"))
    )
    (net (code "84") (name "Net-(U$4-P$3)") (class "Default")
      (node (ref "R13") (pin "2") (pinfunction "2_2") (pintype "passive"))
      (node (ref "U$4") (pin "P$9") (pinfunction "P$3_P$9") (pintype "bidirectional"))
    )
    (net (code "85") (name "Net-(U$4-P$4)") (class "Default")
      (node (ref "R30") (pin "2") (pinfunction "2_2") (pintype "passive"))
      (node (ref "U$4") (pin "P$8") (pinfunction "P$4_P$8") (pintype "bidirectional"))
    )
    (net (code "86") (name "Net-(U$4-P$7)") (class "Default")
      (node (ref "SHLD") (pin "2") (pinfunction "2_2") (pintype "passive"))
      (node (ref "U$4") (pin "P$1") (pinfunction "P$7_P$1") (pintype "bidirectional"))
      (node (ref "U$4") (pin "P$2") (pinfunction "P$8_P$2") (pintype "bidirectional"))
    )
    (net (code "87") (name "Net-(U2-IN)") (class "Default")
      (node (ref "JP4") (pin "1") (pinfunction "1_1") (pintype "passive"))
      (node (ref "U2") (pin "1") (pinfunction "IN_1") (pintype "power_in"))
    )
    (net (code "88") (name "VBUS") (class "Default")
      (node (ref "C26") (pin "2") (pinfunction "2_2") (pintype "passive"))
      (node (ref "D7") (pin "A") (pinfunction "A_A") (pintype "passive"))
      (node (ref "JP2") (pin "1") (pinfunction "1_1") (pintype "passive"))
      (node (ref "JP5") (pin "1") (pinfunction "1_1") (pintype "passive"))
      (node (ref "Q3") (pin "1") (pinfunction "G_1") (pintype "passive"))
      (node (ref "R14") (pin "2") (pinfunction "2_2") (pintype "passive"))
      (node (ref "R16") (pin "2") (pinfunction "2_2") (pintype "passive"))
      (node (ref "U$4") (pin "P$6") (pinfunction "P$2_P$6") (pintype "bidirectional"))
      (node (ref "U$4") (pin "P$7") (pinfunction "P$5_P$7") (pintype "bidirectional"))
      (node (ref "U1") (pin "4") (pinfunction "4_4") (pintype "bidirectional"))
      (node (ref "U1") (pin "8") (pinfunction "8_8") (pintype "bidirectional"))
    )
    (net (code "89") (name "unconnected-(J4-PAD1-PadNC1)") (class "Default")
      (node (ref "J4") (pin "NC1") (pinfunction "PAD1_NC1") (pintype "bidirectional"))
    )
    (net (code "90") (name "unconnected-(J4-PAD2-PadNC2)") (class "Default")
      (node (ref "J4") (pin "NC2") (pinfunction "PAD2_NC2") (pintype "bidirectional"))
    )
    (net (code "91") (name "unconnected-(J5-PAD1-PadNC1)") (class "Default")
      (node (ref "J5") (pin "NC1") (pinfunction "PAD1_NC1") (pintype "bidirectional"))
    )
    (net (code "92") (name "unconnected-(J5-PAD2-PadNC2)") (class "Default")
      (node (ref "J5") (pin "NC2") (pinfunction "PAD2_NC2") (pintype "bidirectional"))
    )
    (net (code "93") (name "unconnected-(P1AH-1-Pad4)") (class "Default")
      (node (ref "P1") (pin "4") (pinfunction "1_4") (pintype "passive"))
    )
    (net (code "94") (name "unconnected-(P1AM-1-Pad44)") (class "Default")
      (node (ref "P1") (pin "44") (pinfunction "1_44") (pintype "passive"))
    )
    (net (code "95") (name "unconnected-(P1AT-1-Pad50)") (class "Default")
      (node (ref "P1") (pin "50") (pinfunction "1_50") (pintype "passive"))
    )
    (net (code "96") (name "unconnected-(P1D-1-Pad12)") (class "Default")
      (node (ref "P1") (pin "12") (pinfunction "1_12") (pintype "passive"))
    )
    (net (code "97") (name "unconnected-(P1G-1-Pad15)") (class "Default")
      (node (ref "P1") (pin "15") (pinfunction "1_15") (pintype "passive"))
    )
    (net (code "98") (name "unconnected-(P1H-1-Pad16)") (class "Default")
      (node (ref "P1") (pin "16") (pinfunction "1_16") (pintype "passive"))
    )
    (net (code "99") (name "unconnected-(P1I-1-Pad17)") (class "Default")
      (node (ref "P1") (pin "17") (pinfunction "1_17") (pintype "passive"))
    )
    (net (code "100") (name "unconnected-(P1S-1-Pad26)") (class "Default")
      (node (ref "P1") (pin "26") (pinfunction "1_26") (pintype "passive"))
    )
    (net (code "101") (name "unconnected-(P1T-1-Pad27)") (class "Default")
      (node (ref "P1") (pin "27") (pinfunction "1_27") (pintype "passive"))
    )
    (net (code "102") (name "unconnected-(P1W-1-Pad3)") (class "Default")
      (node (ref "P1") (pin "3") (pinfunction "1_3") (pintype "passive"))
    )
    (net (code "103") (name "unconnected-(U2-P4-Pad4)") (class "Default")
      (node (ref "U2") (pin "4") (pinfunction "P4_4") (pintype "bidirectional"))
    )
    (net (code "104") (name "unconnected-(U3-POCI3{slash}IO19-Pad31)") (class "Default")
      (node (ref "U3") (pin "31") (pinfunction "POCI3/IO19_31") (pintype "bidirectional"))
    )
    (net (code "105") (name "unconnected-(U4-P4-Pad4)") (class "Default")
      (node (ref "U4") (pin "4") (pinfunction "P4_4") (pintype "bidirectional"))
    )
  )
)
